# fillcap_sensor.net
KiCad netlist of a schematic drawn in Altium Designer
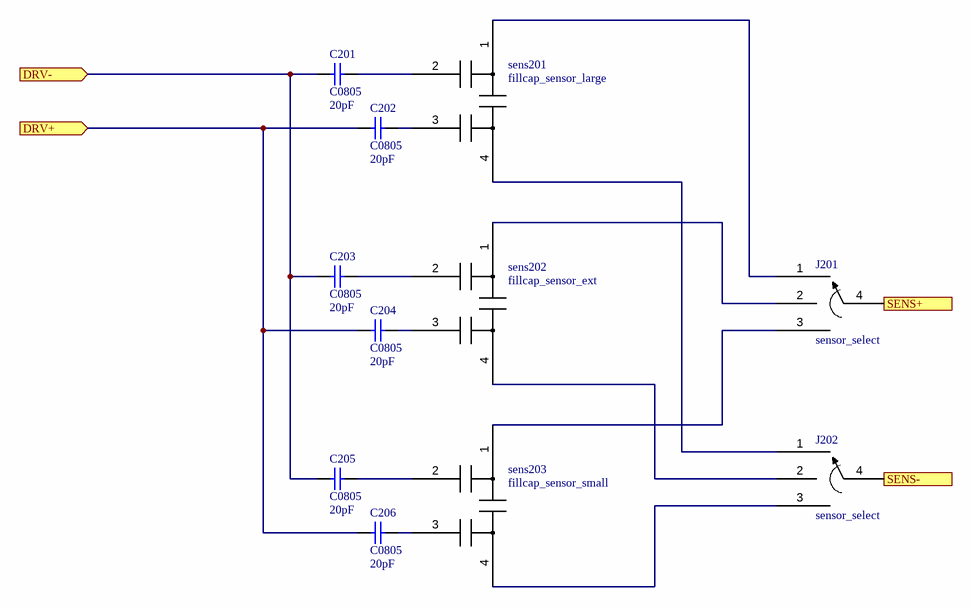
[diagram p0: fillcap_sensor.SchDoc]

(export (version "E")
  (design (tool "Eeschema 10.0.6"))
  (components
    (comp (ref "C201")
      (value "C0805")
      (footprint "0805")
      (description "Ceramic Chip Capacitor - Standard")
      (fields (field (name "ALTIUM_VALUE") "20pF") (field (name "PUBLISHER") "Altium Limited"))
      (libsource (lib "KEMET Chip Capacitor") (part "C0805"))
    )
    (comp (ref "C202")
      (value "C0805")
      (footprint "0805")
      (description "Ceramic Chip Capacitor - Standard")
      (fields (field (name "ALTIUM_VALUE") "20pF") (field (name "PUBLISHER") "Altium Limited"))
      (libsource (lib "KEMET Chip Capacitor") (part "C0805"))
    )
    (comp (ref "C203")
      (value "C0805")
      (footprint "0805")
      (description "Ceramic Chip Capacitor - Standard")
      (fields (field (name "ALTIUM_VALUE") "20pF") (field (name "PUBLISHER") "Altium Limited"))
      (libsource (lib "KEMET Chip Capacitor") (part "C0805"))
    )
    (comp (ref "C204")
      (value "C0805")
      (footprint "0805")
      (description "Ceramic Chip Capacitor - Standard")
      (fields (field (name "ALTIUM_VALUE") "20pF") (field (name "PUBLISHER") "Altium Limited"))
      (libsource (lib "KEMET Chip Capacitor") (part "C0805"))
    )
    (comp (ref "C205")
      (value "C0805")
      (footprint "0805")
      (description "Ceramic Chip Capacitor - Standard")
      (fields (field (name "ALTIUM_VALUE") "20pF") (field (name "PUBLISHER") "Altium Limited"))
      (libsource (lib "KEMET Chip Capacitor") (part "C0805"))
    )
    (comp (ref "C206")
      (value "C0805")
      (footprint "0805")
      (description "Ceramic Chip Capacitor - Standard")
      (fields (field (name "ALTIUM_VALUE") "20pF") (field (name "PUBLISHER") "Altium Limited"))
      (libsource (lib "KEMET Chip Capacitor") (part "C0805"))
    )
    (comp (ref "J201")
      (value "sensor_select")
      (footprint "sens_select_jumper")
      (libsource (lib "fillcap_lib") (part "sensor_select"))
    )
    (comp (ref "J202")
      (value "sensor_select")
      (footprint "sens_select_jumper")
      (libsource (lib "fillcap_lib") (part "sensor_select"))
    )
    (comp (ref "sens201")
      (value "fillcap_sensor_large")
      (footprint "fillcap_sensor_large")
      (libsource (lib "fillcap_lib") (part "fillcap_sensor"))
    )
    (comp (ref "sens202")
      (value "fillcap_sensor_ext")
      (footprint "fillcap_sensor_ext")
      (libsource (lib "fillcap_lib") (part "fillcap_sensor"))
    )
    (comp (ref "sens203")
      (value "fillcap_sensor_small")
      (footprint "fillcap_sensor_small")
      (libsource (lib "fillcap_lib") (part "fillcap_sensor"))
    )
  )
  (nets
    (net (code "1") (name "/DRV+") (class "Default")
      (node (ref "C202") (pin "2") (pinfunction "2_2") (pintype "passive"))
      (node (ref "C204") (pin "2") (pinfunction "2_2") (pintype "passive"))
      (node (ref "C206") (pin "2") (pinfunction "2_2") (pintype "passive"))
    )
    (net (code "2") (name "/DRV-") (class "Default")
      (node (ref "C201") (pin "2") (pinfunction "2_2") (pintype "passive"))
      (node (ref "C203") (pin "2") (pinfunction "2_2") (pintype "passive"))
      (node (ref "C205") (pin "2") (pinfunction "2_2") (pintype "passive"))
    )
    (net (code "3") (name "/SENS+") (class "Default")
      (node (ref "J201") (pin "4") (pinfunction "4_4") (pintype "passive"))
    )
    (net (code "4") (name "/SENS-") (class "Default")
      (node (ref "J202") (pin "4") (pinfunction "4_4") (pintype "passive"))
    )
    (net (code "5") (name "Net-(C201-Pad1)") (class "Default")
      (node (ref "C201") (pin "1") (pinfunction "1_1") (pintype "passive"))
      (node (ref "sens201") (pin "2") (pinfunction "2_2") (pintype "passive"))
    )
    (net (code "6") (name "Net-(C202-Pad1)") (class "Default")
      (node (ref "C202") (pin "1") (pinfunction "1_1") (pintype "passive"))
      (node (ref "sens201") (pin "3") (pinfunction "3_3") (pintype "passive"))
    )
    (net (code "7") (name "Net-(C203-Pad1)") (class "Default")
      (node (ref "C203") (pin "1") (pinfunction "1_1") (pintype "passive"))
      (node (ref "sens202") (pin "2") (pinfunction "2_2") (pintype "passive"))
    )
    (net (code "8") (name "Net-(C204-Pad1)") (class "Default")
      (node (ref "C204") (pin "1") (pinfunction "1_1") (pintype "passive"))
      (node (ref "sens202") (pin "3") (pinfunction "3_3") (pintype "passive"))
    )
    (net (code "9") (name "Net-(C205-Pad1)") (class "Default")
      (node (ref "C205") (pin "1") (pinfunction "1_1") (pintype "passive"))
      (node (ref "sens203") (pin "2") (pinfunction "2_2") (pintype "passive"))
    )
    (net (code "10") (name "Net-(C206-Pad1)") (class "Default")
      (node (ref "C206") (pin "1") (pinfunction "1_1") (pintype "passive"))
      (node (ref "sens203") (pin "3") (pinfunction "3_3") (pintype "passive"))
    )
    (net (code "11") (name "Net-(J201-Pad1)") (class "Default")
      (node (ref "J201") (pin "1") (pinfunction "1_1") (pintype "passive"))
      (node (ref "sens201") (pin "1") (pinfunction "1_1") (pintype "passive"))
    )
    (net (code "12") (name "Net-(J201-Pad2)") (class "Default")
      (node (ref "J201") (pin "2") (pinfunction "2_2") (pintype "passive"))
      (node (ref "sens202") (pin "1") (pinfunction "1_1") (pintype "passive"))
    )
    (net (code "13") (name "Net-(J201-Pad3)") (class "Default")
      (node (ref "J201") (pin "3") (pinfunction "3_3") (pintype "passive"))
      (node (ref "sens203") (pin "1") (pinfunction "1_1") (pintype "passive"))
    )
    (net (code "14") (name "Net-(J202-Pad1)") (class "Default")
      (node (ref "J202") (pin "1") (pinfunction "1_1") (pintype "passive"))
      (node (ref "sens201") (pin "4") (pinfunction "4_4") (pintype "passive"))
    )
    (net (code "15") (name "Net-(J202-Pad2)") (class "Default")
      (node (ref "J202") (pin "2") (pinfunction "2_2") (pintype "passive"))
      (node (ref "sens202") (pin "4") (pinfunction "4_4") (pintype "passive"))
    )
    (net (code "16") (name "Net-(J202-Pad3)") (class "Default")
      (node (ref "J202") (pin "3") (pinfunction "3_3") (pintype "passive"))
      (node (ref "sens203") (pin "4") (pinfunction "4_4") (pintype "passive"))
    )
  )
)
